# controller.net
KiCad netlist of a schematic drawn in EAGLE
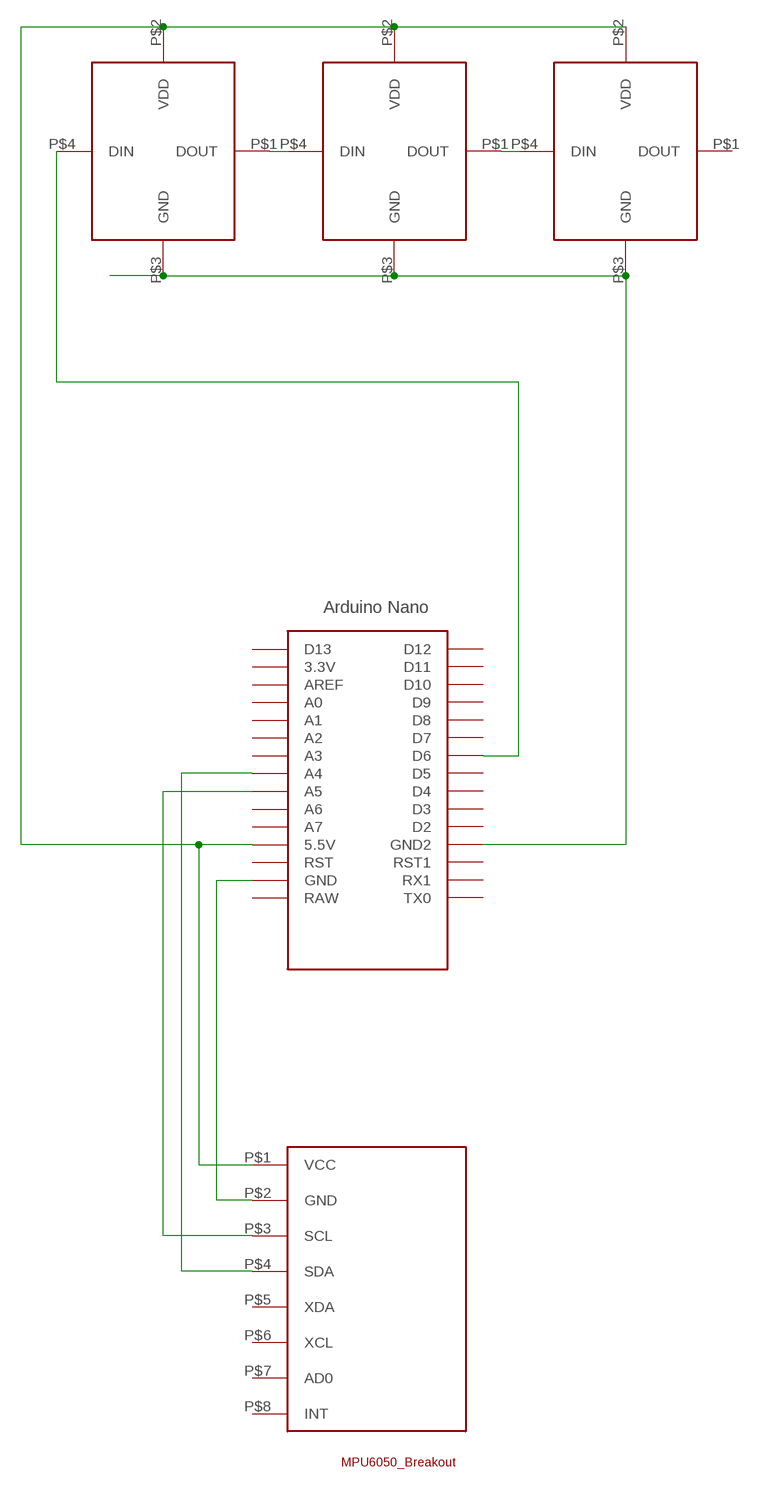
[diagram p0: schematic, sheet 1]

(export (version "E")
  (design (tool "Eeschema 10.0.6"))
  (components
    (comp (ref "U$1")
      (value "NANO")
      (footprint "eagle-import:NANO")
      (libsource (lib "eagle-import") (part "NANO"))
    )
    (comp (ref "U$2")
      (value "NEOPIXEL_8MM")
      (footprint "eagle-import:NEOPIXEL_8MM")
      (libsource (lib "eagle-import") (part "NEOPIXEL_8MM"))
    )
    (comp (ref "U$3")
      (value "NEOPIXEL_8MM")
      (footprint "eagle-import:NEOPIXEL_8MM")
      (libsource (lib "eagle-import") (part "NEOPIXEL_8MM"))
    )
    (comp (ref "U$4")
      (value "NEOPIXEL_8MM")
      (footprint "eagle-import:NEOPIXEL_8MM")
      (libsource (lib "eagle-import") (part "NEOPIXEL_8MM"))
    )
    (comp (ref "U$5")
      (value "MPU6050_BREAKOUT")
      (footprint "eagle-import:MPU6050")
      (libsource (lib "eagle-import") (part "MPU6050_BREAKOUT"))
    )
  )
  (nets
    (net (code "1") (name "Net-(U$1-5.5V)") (class "Default")
      (node (ref "U$1") (pin "5V") (pinfunction "5.5V_5V") (pintype "bidirectional"))
      (node (ref "U$2") (pin "P$2") (pinfunction "VDD_P$2") (pintype "bidirectional"))
      (node (ref "U$3") (pin "P$2") (pinfunction "VDD_P$2") (pintype "bidirectional"))
      (node (ref "U$4") (pin "P$2") (pinfunction "VDD_P$2") (pintype "bidirectional"))
      (node (ref "U$5") (pin "P$1") (pinfunction "VCC_P$1") (pintype "bidirectional"))
    )
    (net (code "2") (name "Net-(U$1-GND2)") (class "Default")
      (node (ref "U$1") (pin "GND1") (pinfunction "GND2_GND1") (pintype "bidirectional"))
      (node (ref "U$2") (pin "P$3") (pinfunction "GND_P$3") (pintype "bidirectional"))
      (node (ref "U$3") (pin "P$3") (pinfunction "GND_P$3") (pintype "bidirectional"))
      (node (ref "U$4") (pin "P$3") (pinfunction "GND_P$3") (pintype "bidirectional"))
    )
    (net (code "3") (name "Net-(U$2-DIN)") (class "Default")
      (node (ref "U$1") (pin "D6") (pinfunction "D6_D6") (pintype "bidirectional"))
      (node (ref "U$2") (pin "P$4") (pinfunction "DIN_P$4") (pintype "bidirectional"))
    )
    (net (code "4") (name "Net-(U$2-DOUT)") (class "Default")
      (node (ref "U$2") (pin "P$1") (pinfunction "DOUT_P$1") (pintype "bidirectional"))
      (node (ref "U$3") (pin "P$4") (pinfunction "DIN_P$4") (pintype "bidirectional"))
    )
    (net (code "5") (name "Net-(U$3-DOUT)") (class "Default")
      (node (ref "U$3") (pin "P$1") (pinfunction "DOUT_P$1") (pintype "bidirectional"))
      (node (ref "U$4") (pin "P$4") (pinfunction "DIN_P$4") (pintype "bidirectional"))
    )
    (net (code "6") (name "Net-(U$5-GND)") (class "Default")
      (node (ref "U$1") (pin "GND") (pinfunction "GND_GND") (pintype "bidirectional"))
      (node (ref "U$5") (pin "P$2") (pinfunction "GND_P$2") (pintype "bidirectional"))
    )
    (net (code "7") (name "Net-(U$5-SCL)") (class "Default")
      (node (ref "U$1") (pin "A5") (pinfunction "A5_A5") (pintype "bidirectional"))
      (node (ref "U$5") (pin "P$3") (pinfunction "SCL_P$3") (pintype "bidirectional"))
    )
    (net (code "8") (name "Net-(U$5-SDA)") (class "Default")
      (node (ref "U$1") (pin "A4") (pinfunction "A4_A4") (pintype "bidirectional"))
      (node (ref "U$5") (pin "P$4") (pinfunction "SDA_P$4") (pintype "bidirectional"))
    )
    (net (code "9") (name "unconnected-(U$1-Pad3.3V)") (class "Default")
      (node (ref "U$1") (pin "3.3V") (pinfunction "3.3V_3.3V") (pintype "bidirectional"))
    )
    (net (code "10") (name "unconnected-(U$1-PadA0)") (class "Default")
      (node (ref "U$1") (pin "A0") (pinfunction "A0_A0") (pintype "bidirectional"))
    )
    (net (code "11") (name "unconnected-(U$1-PadA1)") (class "Default")
      (node (ref "U$1") (pin "A1") (pinfunction "A1_A1") (pintype "bidirectional"))
    )
    (net (code "12") (name "unconnected-(U$1-PadA2)") (class "Default")
      (node (ref "U$1") (pin "A2") (pinfunction "A2_A2") (pintype "bidirectional"))
    )
    (net (code "13") (name "unconnected-(U$1-PadA3)") (class "Default")
      (node (ref "U$1") (pin "A3") (pinfunction "A3_A3") (pintype "bidirectional"))
    )
    (net (code "14") (name "unconnected-(U$1-PadA6)") (class "Default")
      (node (ref "U$1") (pin "A6") (pinfunction "A6_A6") (pintype "bidirectional"))
    )
    (net (code "15") (name "unconnected-(U$1-PadA7)") (class "Default")
      (node (ref "U$1") (pin "A7") (pinfunction "A7_A7") (pintype "bidirectional"))
    )
    (net (code "16") (name "unconnected-(U$1-PadAREF)") (class "Default")
      (node (ref "U$1") (pin "AREF") (pinfunction "AREF_AREF") (pintype "bidirectional"))
    )
    (net (code "17") (name "unconnected-(U$1-PadD2)") (class "Default")
      (node (ref "U$1") (pin "D2") (pinfunction "D2_D2") (pintype "bidirectional"))
    )
    (net (code "18") (name "unconnected-(U$1-PadD3)") (class "Default")
      (node (ref "U$1") (pin "D3") (pinfunction "D3_D3") (pintype "bidirectional"))
    )
    (net (code "19") (name "unconnected-(U$1-PadD4)") (class "Default")
      (node (ref "U$1") (pin "D4") (pinfunction "D4_D4") (pintype "bidirectional"))
    )
    (net (code "20") (name "unconnected-(U$1-PadD5)") (class "Default")
      (node (ref "U$1") (pin "D5") (pinfunction "D5_D5") (pintype "bidirectional"))
    )
    (net (code "21") (name "unconnected-(U$1-PadD7)") (class "Default")
      (node (ref "U$1") (pin "D7") (pinfunction "D7_D7") (pintype "bidirectional"))
    )
    (net (code "22") (name "unconnected-(U$1-PadD8)") (class "Default")
      (node (ref "U$1") (pin "D8") (pinfunction "D8_D8") (pintype "bidirectional"))
    )
    (net (code "23") (name "unconnected-(U$1-PadD9)") (class "Default")
      (node (ref "U$1") (pin "D9") (pinfunction "D9_D9") (pintype "bidirectional"))
    )
    (net (code "24") (name "unconnected-(U$1-PadD10)") (class "Default")
      (node (ref "U$1") (pin "D10") (pinfunction "D10_D10") (pintype "bidirectional"))
    )
    (net (code "25") (name "unconnected-(U$1-PadD11)") (class "Default")
      (node (ref "U$1") (pin "D11") (pinfunction "D11_D11") (pintype "bidirectional"))
    )
    (net (code "26") (name "unconnected-(U$1-PadD12)") (class "Default")
      (node (ref "U$1") (pin "D12") (pinfunction "D12_D12") (pintype "bidirectional"))
    )
    (net (code "27") (name "unconnected-(U$1-PadD13)") (class "Default")
      (node (ref "U$1") (pin "D13") (pinfunction "D13_D13") (pintype "bidirectional"))
    )
    (net (code "28") (name "unconnected-(U$1-PadICSP1)") (class "Default")
      (node (ref "U$1") (pin "ICSP1") (pinfunction "ICSP1_ICSP1") (pintype "bidirectional"))
    )
    (net (code "29") (name "unconnected-(U$1-PadICSP2)") (class "Default")
      (node (ref "U$1") (pin "ICSP2") (pinfunction "ICSP2_ICSP2") (pintype "bidirectional"))
    )
    (net (code "30") (name "unconnected-(U$1-PadICSP3)") (class "Default")
      (node (ref "U$1") (pin "ICSP3") (pinfunction "ICSP3_ICSP3") (pintype "bidirectional"))
    )
    (net (code "31") (name "unconnected-(U$1-PadICSP4)") (class "Default")
      (node (ref "U$1") (pin "ICSP4") (pinfunction "ICSP4_ICSP4") (pintype "bidirectional"))
    )
    (net (code "32") (name "unconnected-(U$1-PadICSP5)") (class "Default")
      (node (ref "U$1") (pin "ICSP5") (pinfunction "ICSP5_ICSP5") (pintype "bidirectional"))
    )
    (net (code "33") (name "unconnected-(U$1-PadICSP6)") (class "Default")
      (node (ref "U$1") (pin "ICSP6") (pinfunction "ICSP6_ICSP6") (pintype "bidirectional"))
    )
    (net (code "34") (name "unconnected-(U$1-PadRAW)") (class "Default")
      (node (ref "U$1") (pin "RAW") (pinfunction "RAW_RAW") (pintype "bidirectional"))
    )
    (net (code "35") (name "unconnected-(U$1-PadRST)") (class "Default")
      (node (ref "U$1") (pin "RST") (pinfunction "RST_RST") (pintype "bidirectional"))
    )
    (net (code "36") (name "unconnected-(U$1-PadRST1)") (class "Default")
      (node (ref "U$1") (pin "RST1") (pinfunction "RST1_RST1") (pintype "bidirectional"))
    )
    (net (code "37") (name "unconnected-(U$1-PadRX1)") (class "Default")
      (node (ref "U$1") (pin "RX1") (pinfunction "RX1_RX1") (pintype "bidirectional"))
    )
    (net (code "38") (name "unconnected-(U$1-PadTX0)") (class "Default")
      (node (ref "U$1") (pin "TX0") (pinfunction "TX0_TX0") (pintype "bidirectional"))
    )
    (net (code "39") (name "unconnected-(U$4-DOUT-PadP$1)") (class "Default")
      (node (ref "U$4") (pin "P$1") (pinfunction "DOUT_P$1") (pintype "bidirectional"))
    )
    (net (code "40") (name "unconnected-(U$5-AD0-PadP$7)") (class "Default")
      (node (ref "U$5") (pin "P$7") (pinfunction "AD0_P$7") (pintype "bidirectional"))
    )
    (net (code "41") (name "unconnected-(U$5-INT-PadP$8)") (class "Default")
      (node (ref "U$5") (pin "P$8") (pinfunction "INT_P$8") (pintype "bidirectional"))
    )
    (net (code "42") (name "unconnected-(U$5-XCL-PadP$6)") (class "Default")
      (node (ref "U$5") (pin "P$6") (pinfunction "XCL_P$6") (pintype "bidirectional"))
    )
    (net (code "43") (name "unconnected-(U$5-XDA-PadP$5)") (class "Default")
      (node (ref "U$5") (pin "P$5") (pinfunction "XDA_P$5") (pintype "bidirectional"))
    )
  )
)
